# TeensyBufferWithNetworks.net
KiCad netlist of a schematic drawn in EAGLE
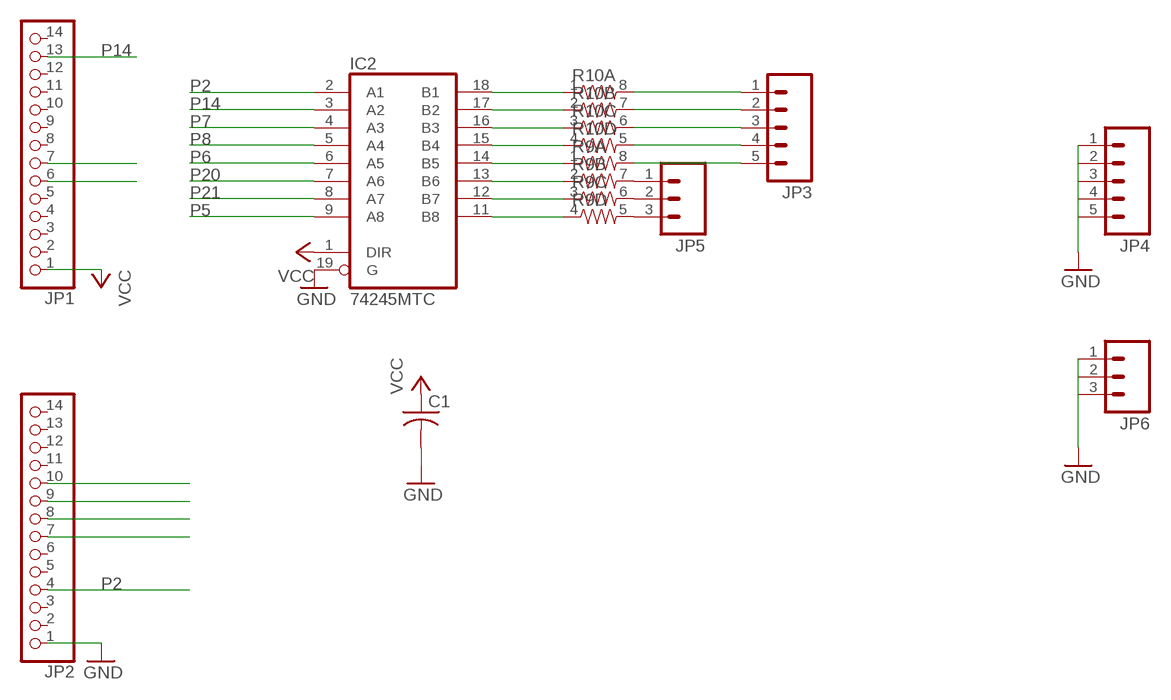
[diagram p0: schematic, sheet 1]

(export (version "E")
  (design (tool "Eeschema 10.0.6"))
  (components
    (comp (ref "C1")
      (value "C-USC0805")
      (footprint "eagle-import:C0805")
      (libsource (lib "eagle-import") (part "C-USC0805"))
    )
    (comp (ref "IC2")
      (value "74245MTC")
      (footprint "eagle-import:SSOP20")
      (libsource (lib "eagle-import") (part "74245MTC"))
    )
    (comp (ref "JP1")
      (value "PINHD-1X14-CB")
      (footprint "eagle-import:1X14-CB")
      (libsource (lib "eagle-import") (part "PINHD-1X14-CB"))
    )
    (comp (ref "JP2")
      (value "PINHD-1X14-CB")
      (footprint "eagle-import:1X14-CB")
      (libsource (lib "eagle-import") (part "PINHD-1X14-CB"))
    )
    (comp (ref "JP3")
      (value "M05NO_SILK")
      (footprint "eagle-import:1X05_NO_SILK")
      (libsource (lib "eagle-import") (part "M05NO_SILK"))
    )
    (comp (ref "JP4")
      (value "M05NO_SILK")
      (footprint "eagle-import:1X05_NO_SILK")
      (libsource (lib "eagle-import") (part "M05NO_SILK"))
    )
    (comp (ref "JP5")
      (value "M031X03_NO_SILK")
      (footprint "eagle-import:1X03_NO_SILK")
      (libsource (lib "eagle-import") (part "M031X03_NO_SILK"))
    )
    (comp (ref "JP6")
      (value "M031X03_NO_SILK")
      (footprint "eagle-import:1X03_NO_SILK")
      (libsource (lib "eagle-import") (part "M031X03_NO_SILK"))
    )
    (comp (ref "R9")
      (value "RESISTOR-ARRAY0603-ARV")
      (footprint "eagle-import:0603-ARV")
      (libsource (lib "eagle-import") (part "RESISTOR-ARRAY0603-ARV"))
    )
    (comp (ref "R10")
      (value "RESISTOR-ARRAY0603-ARV")
      (footprint "eagle-import:0603-ARV")
      (libsource (lib "eagle-import") (part "RESISTOR-ARRAY0603-ARV"))
    )
  )
  (nets
    (net (code "1") (name "/P2") (class "Default")
      (node (ref "IC2") (pin "2") (pinfunction "A1_2") (pintype "bidirectional"))
      (node (ref "JP2") (pin "4") (pinfunction "4_4") (pintype "passive"))
    )
    (net (code "2") (name "/P5") (class "Default")
      (node (ref "IC2") (pin "9") (pinfunction "A8_9") (pintype "bidirectional"))
      (node (ref "JP2") (pin "7") (pinfunction "7_7") (pintype "passive"))
    )
    (net (code "3") (name "/P6") (class "Default")
      (node (ref "IC2") (pin "6") (pinfunction "A5_6") (pintype "bidirectional"))
      (node (ref "JP2") (pin "8") (pinfunction "8_8") (pintype "passive"))
    )
    (net (code "4") (name "/P7") (class "Default")
      (node (ref "IC2") (pin "4") (pinfunction "A3_4") (pintype "bidirectional"))
      (node (ref "JP2") (pin "9") (pinfunction "9_9") (pintype "passive"))
    )
    (net (code "5") (name "/P8") (class "Default")
      (node (ref "IC2") (pin "5") (pinfunction "A4_5") (pintype "bidirectional"))
      (node (ref "JP2") (pin "10") (pinfunction "10_10") (pintype "passive"))
    )
    (net (code "6") (name "/P14") (class "Default")
      (node (ref "IC2") (pin "3") (pinfunction "A2_3") (pintype "bidirectional"))
      (node (ref "JP1") (pin "13") (pinfunction "13_13") (pintype "passive"))
    )
    (net (code "7") (name "/P20") (class "Default")
      (node (ref "IC2") (pin "7") (pinfunction "A6_7") (pintype "bidirectional"))
      (node (ref "JP1") (pin "7") (pinfunction "7_7") (pintype "passive"))
    )
    (net (code "8") (name "/P21") (class "Default")
      (node (ref "IC2") (pin "8") (pinfunction "A7_8") (pintype "bidirectional"))
      (node (ref "JP1") (pin "6") (pinfunction "6_6") (pintype "passive"))
    )
    (net (code "9") (name "GND") (class "Default")
      (node (ref "C1") (pin "2") (pinfunction "2_2") (pintype "passive"))
      (node (ref "IC2") (pin "19") (pinfunction "G_19") (pintype "input"))
      (node (ref "JP2") (pin "1") (pinfunction "1_1") (pintype "passive"))
      (node (ref "JP4") (pin "1") (pinfunction "1_1") (pintype "passive"))
      (node (ref "JP4") (pin "2") (pinfunction "2_2") (pintype "passive"))
      (node (ref "JP4") (pin "3") (pinfunction "3_3") (pintype "passive"))
      (node (ref "JP4") (pin "4") (pinfunction "4_4") (pintype "passive"))
      (node (ref "JP4") (pin "5") (pinfunction "5_5") (pintype "passive"))
      (node (ref "JP6") (pin "1") (pinfunction "1_1") (pintype "passive"))
      (node (ref "JP6") (pin "2") (pinfunction "2_2") (pintype "passive"))
      (node (ref "JP6") (pin "3") (pinfunction "3_3") (pintype "passive"))
    )
    (net (code "10") (name "Net-(IC2A-B1)") (class "Default")
      (node (ref "IC2") (pin "18") (pinfunction "B1_18") (pintype "bidirectional"))
      (node (ref "R10") (pin "1") (pinfunction "1_1") (pintype "passive"))
    )
    (net (code "11") (name "Net-(IC2A-B2)") (class "Default")
      (node (ref "IC2") (pin "17") (pinfunction "B2_17") (pintype "bidirectional"))
      (node (ref "R10") (pin "2") (pinfunction "1_2") (pintype "passive"))
    )
    (net (code "12") (name "Net-(IC2A-B3)") (class "Default")
      (node (ref "IC2") (pin "16") (pinfunction "B3_16") (pintype "bidirectional"))
      (node (ref "R10") (pin "3") (pinfunction "1_3") (pintype "passive"))
    )
    (net (code "13") (name "Net-(IC2A-B4)") (class "Default")
      (node (ref "IC2") (pin "15") (pinfunction "B4_15") (pintype "bidirectional"))
      (node (ref "R10") (pin "4") (pinfunction "1_4") (pintype "passive"))
    )
    (net (code "14") (name "Net-(IC2A-B5)") (class "Default")
      (node (ref "IC2") (pin "14") (pinfunction "B5_14") (pintype "bidirectional"))
      (node (ref "R9") (pin "1") (pinfunction "1_1") (pintype "passive"))
    )
    (net (code "15") (name "Net-(IC2A-B6)") (class "Default")
      (node (ref "IC2") (pin "13") (pinfunction "B6_13") (pintype "bidirectional"))
      (node (ref "R9") (pin "2") (pinfunction "1_2") (pintype "passive"))
    )
    (net (code "16") (name "Net-(IC2A-B7)") (class "Default")
      (node (ref "IC2") (pin "12") (pinfunction "B7_12") (pintype "bidirectional"))
      (node (ref "R9") (pin "3") (pinfunction "1_3") (pintype "passive"))
    )
    (net (code "17") (name "Net-(IC2A-B8)") (class "Default")
      (node (ref "IC2") (pin "11") (pinfunction "B8_11") (pintype "bidirectional"))
      (node (ref "R9") (pin "4") (pinfunction "1_4") (pintype "passive"))
    )
    (net (code "18") (name "Net-(R9A-2)") (class "Default")
      (node (ref "JP3") (pin "5") (pinfunction "5_5") (pintype "passive"))
      (node (ref "R9") (pin "8") (pinfunction "2_8") (pintype "passive"))
    )
    (net (code "19") (name "Net-(R9B-2)") (class "Default")
      (node (ref "JP5") (pin "1") (pinfunction "1_1") (pintype "passive"))
      (node (ref "R9") (pin "7") (pinfunction "2_7") (pintype "passive"))
    )
    (net (code "20") (name "Net-(R9C-2)") (class "Default")
      (node (ref "JP5") (pin "2") (pinfunction "2_2") (pintype "passive"))
      (node (ref "R9") (pin "6") (pinfunction "2_6") (pintype "passive"))
    )
    (net (code "21") (name "Net-(R9D-2)") (class "Default")
      (node (ref "JP5") (pin "3") (pinfunction "3_3") (pintype "passive"))
      (node (ref "R9") (pin "5") (pinfunction "2_5") (pintype "passive"))
    )
    (net (code "22") (name "Net-(R10A-2)") (class "Default")
      (node (ref "JP3") (pin "1") (pinfunction "1_1") (pintype "passive"))
      (node (ref "R10") (pin "8") (pinfunction "2_8") (pintype "passive"))
    )
    (net (code "23") (name "Net-(R10B-2)") (class "Default")
      (node (ref "JP3") (pin "2") (pinfunction "2_2") (pintype "passive"))
      (node (ref "R10") (pin "7") (pinfunction "2_7") (pintype "passive"))
    )
    (net (code "24") (name "Net-(R10C-2)") (class "Default")
      (node (ref "JP3") (pin "3") (pinfunction "3_3") (pintype "passive"))
      (node (ref "R10") (pin "6") (pinfunction "2_6") (pintype "passive"))
    )
    (net (code "25") (name "Net-(R10D-2)") (class "Default")
      (node (ref "JP3") (pin "4") (pinfunction "4_4") (pintype "passive"))
      (node (ref "R10") (pin "5") (pinfunction "2_5") (pintype "passive"))
    )
    (net (code "26") (name "VCC") (class "Default")
      (node (ref "C1") (pin "1") (pinfunction "1_1") (pintype "passive"))
      (node (ref "IC2") (pin "1") (pinfunction "DIR_1") (pintype "input"))
      (node (ref "JP1") (pin "1") (pinfunction "1_1") (pintype "passive"))
    )
    (net (code "27") (name "unconnected-(JP1-Pad2)") (class "Default")
      (node (ref "JP1") (pin "2") (pinfunction "2_2") (pintype "passive"))
    )
    (net (code "28") (name "unconnected-(JP1-Pad3)") (class "Default")
      (node (ref "JP1") (pin "3") (pinfunction "3_3") (pintype "passive"))
    )
    (net (code "29") (name "unconnected-(JP1-Pad4)") (class "Default")
      (node (ref "JP1") (pin "4") (pinfunction "4_4") (pintype "passive"))
    )
    (net (code "30") (name "unconnected-(JP1-Pad5)") (class "Default")
      (node (ref "JP1") (pin "5") (pinfunction "5_5") (pintype "passive"))
    )
    (net (code "31") (name "unconnected-(JP1-Pad8)") (class "Default")
      (node (ref "JP1") (pin "8") (pinfunction "8_8") (pintype "passive"))
    )
    (net (code "32") (name "unconnected-(JP1-Pad9)") (class "Default")
      (node (ref "JP1") (pin "9") (pinfunction "9_9") (pintype "passive"))
    )
    (net (code "33") (name "unconnected-(JP1-Pad10)") (class "Default")
      (node (ref "JP1") (pin "10") (pinfunction "10_10") (pintype "passive"))
    )
    (net (code "34") (name "unconnected-(JP1-Pad11)") (class "Default")
      (node (ref "JP1") (pin "11") (pinfunction "11_11") (pintype "passive"))
    )
    (net (code "35") (name "unconnected-(JP1-Pad12)") (class "Default")
      (node (ref "JP1") (pin "12") (pinfunction "12_12") (pintype "passive"))
    )
    (net (code "36") (name "unconnected-(JP1-Pad14)") (class "Default")
      (node (ref "JP1") (pin "14") (pinfunction "14_14") (pintype "passive"))
    )
    (net (code "37") (name "unconnected-(JP2-Pad2)") (class "Default")
      (node (ref "JP2") (pin "2") (pinfunction "2_2") (pintype "passive"))
    )
    (net (code "38") (name "unconnected-(JP2-Pad3)") (class "Default")
      (node (ref "JP2") (pin "3") (pinfunction "3_3") (pintype "passive"))
    )
    (net (code "39") (name "unconnected-(JP2-Pad5)") (class "Default")
      (node (ref "JP2") (pin "5") (pinfunction "5_5") (pintype "passive"))
    )
    (net (code "40") (name "unconnected-(JP2-Pad6)") (class "Default")
      (node (ref "JP2") (pin "6") (pinfunction "6_6") (pintype "passive"))
    )
    (net (code "41") (name "unconnected-(JP2-Pad11)") (class "Default")
      (node (ref "JP2") (pin "11") (pinfunction "11_11") (pintype "passive"))
    )
    (net (code "42") (name "unconnected-(JP2-Pad12)") (class "Default")
      (node (ref "JP2") (pin "12") (pinfunction "12_12") (pintype "passive"))
    )
    (net (code "43") (name "unconnected-(JP2-Pad13)") (class "Default")
      (node (ref "JP2") (pin "13") (pinfunction "13_13") (pintype "passive"))
    )
    (net (code "44") (name "unconnected-(JP2-Pad14)") (class "Default")
      (node (ref "JP2") (pin "14") (pinfunction "14_14") (pintype "passive"))
    )
  )
)
